# 8MHz_Crystal.net
KiCad netlist of a schematic drawn in Altium Designer
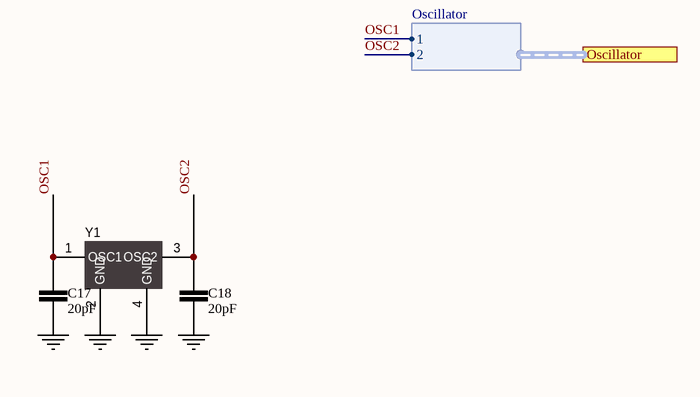
[diagram p0: 8MHz_Crystal.SchDoc]

(export (version "E")
  (design (tool "Eeschema 10.0.6"))
  (components
    (comp (ref "C17")
      (value "20pF")
      (footprint "CER_0603")
      (description "CAP CER 20p 0805")
      (libsource (lib "Capacitors") (part "00002200"))
    )
    (comp (ref "C18")
      (value "20pF")
      (footprint "CER_0603")
      (description "CAP CER 20p 0805")
      (libsource (lib "Capacitors") (part "00002200"))
    )
    (comp (ref "Y1")
      (value "8Hz")
      (footprint "ABM10")
      (description "CRYSTAL 8.0000MHZ 18PF SMD")
      (fields
        (field (name "MANUFACTURER") "ABRACON")
        (field (name "MANUFACTURER PART NUMBER") "ABMM2-8.000MHZ-E2-T")
      )
      (libsource (lib "Discrete_Semiconductor") (part "QUARTZ_8MHz"))
    )
  )
  (nets
    (net (code "2") (name "/OSC1") (class "Default")
      (node (ref "C17") (pin "2") (pinfunction "2_2") (pintype "passive"))
      (node (ref "Y1") (pin "1") (pinfunction "OSC1_1") (pintype "passive"))
    )
    (net (code "3") (name "/OSC2") (class "Default")
      (node (ref "C18") (pin "2") (pinfunction "2_2") (pintype "passive"))
      (node (ref "Y1") (pin "3") (pinfunction "OSC2_3") (pintype "passive"))
    )
    (net (code "5") (name "GND") (class "Default")
      (node (ref "C17") (pin "1") (pinfunction "1_1") (pintype "passive"))
      (node (ref "C18") (pin "1") (pinfunction "1_1") (pintype "passive"))
      (node (ref "Y1") (pin "2") (pinfunction "GND_2") (pintype "passive"))
      (node (ref "Y1") (pin "4") (pinfunction "GND_4") (pintype "passive"))
    )
  )
)
